# Schematic2.net
KiCad netlist of a schematic drawn in Altium Designer
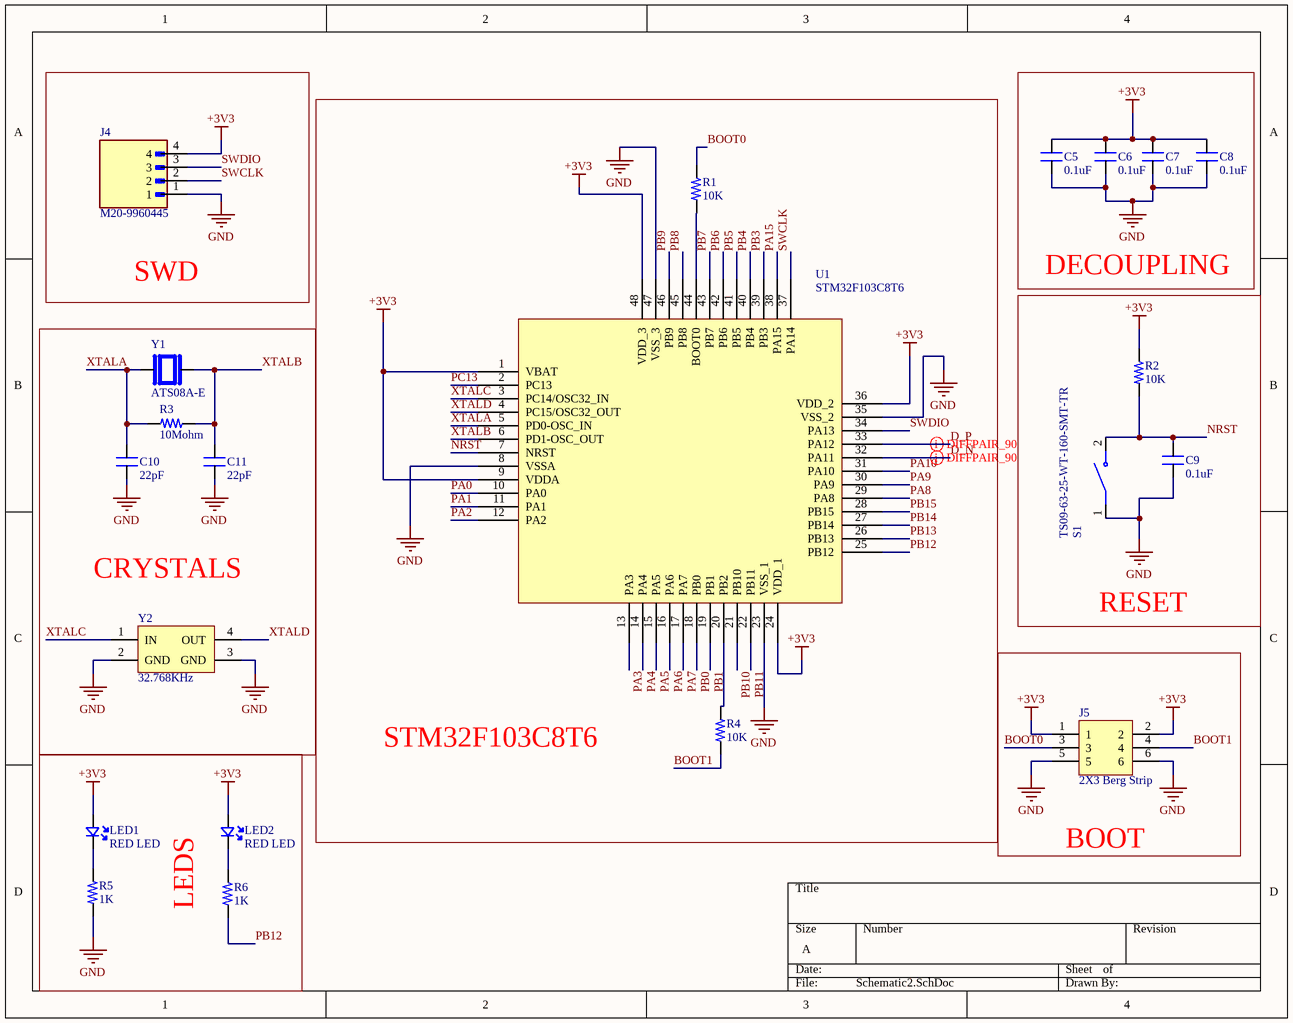
[diagram p0: Schematic2.SchDoc]

(export (version "E")
  (design (tool "Eeschema 10.0.6"))
  (components
    (comp (ref "C5")
      (value "0.1uF")
      (footprint "CAP_0805")
      (description "0.1µF ±5% 50V Ceramic Capacitor X7R 0805 (2012 Metric)")
      (fields
        (field (name "MANUFACTURER") "KEMET")
        (field (name "MANUFACTURING PART NUMBER") "C0805C104J5RACTU")
      )
      (libsource (lib "STM_INT_LIB") (part "CAP_0.1uF-50V-5%-0805"))
    )
    (comp (ref "C6")
      (value "0.1uF")
      (footprint "CAP_0805")
      (description "0.1µF ±5% 50V Ceramic Capacitor X7R 0805 (2012 Metric)")
      (fields
        (field (name "MANUFACTURER") "KEMET")
        (field (name "MANUFACTURING PART NUMBER") "C0805C104J5RACTU")
      )
      (libsource (lib "STM_INT_LIB") (part "CAP_0.1uF-50V-5%-0805"))
    )
    (comp (ref "C7")
      (value "0.1uF")
      (footprint "CAP_0805")
      (description "0.1µF ±5% 50V Ceramic Capacitor X7R 0805 (2012 Metric)")
      (fields
        (field (name "MANUFACTURER") "KEMET")
        (field (name "MANUFACTURING PART NUMBER") "C0805C104J5RACTU")
      )
      (libsource (lib "STM_INT_LIB") (part "CAP_0.1uF-50V-5%-0805"))
    )
    (comp (ref "C8")
      (value "0.1uF")
      (footprint "CAP_0805")
      (description "0.1µF ±5% 50V Ceramic Capacitor X7R 0805 (2012 Metric)")
      (fields
        (field (name "MANUFACTURER") "KEMET")
        (field (name "MANUFACTURING PART NUMBER") "C0805C104J5RACTU")
      )
      (libsource (lib "STM_INT_LIB") (part "CAP_0.1uF-50V-5%-0805"))
    )
    (comp (ref "C9")
      (value "0.1uF")
      (footprint "CAP_0805")
      (description "0.1µF ±5% 50V Ceramic Capacitor X7R 0805 (2012 Metric)")
      (fields
        (field (name "MANUFACTURER") "KEMET")
        (field (name "MANUFACTURING PART NUMBER") "C0805C104J5RACTU")
      )
      (libsource (lib "STM_INT_LIB") (part "CAP_0.1uF-50V-5%-0805"))
    )
    (comp (ref "C10")
      (value "22pF")
      (footprint "CAP_0805")
      (description "22pF ±5% 50V Ceramic Capacitor C0G, NP0 0805 (2012 Metric)")
      (fields
        (field (name "MANUFACTURER") "KEMET")
        (field (name "MANUFACTURER PART NUMBER") "C0805C220J5GACTU")
      )
      (libsource (lib "STM_INT_LIB") (part "CAP_22pF-50V-5%-0805"))
    )
    (comp (ref "C11")
      (value "22pF")
      (footprint "CAP_0805")
      (description "22pF ±5% 50V Ceramic Capacitor C0G, NP0 0805 (2012 Metric)")
      (fields
        (field (name "MANUFACTURER") "KEMET")
        (field (name "MANUFACTURER PART NUMBER") "C0805C220J5GACTU")
      )
      (libsource (lib "STM_INT_LIB") (part "CAP_22pF-50V-5%-0805"))
    )
    (comp (ref "J4")
      (value "M20-9960445")
      (footprint "HARWIN_M20-9960445")
      (fields (field (name "MF") "Harwin"))
      (libsource (lib "4 pin horizontal header") (part "M20-9960445"))
    )
    (comp (ref "J5")
      (value "2X3 Berg Strip")
      (footprint "CON6_100_59D78_TH_ST_Duplicate")
      (description "6 pin, 2 row, 2.54mm pitch bergstrip")
      (fields (field (name "MANUFACTURER") "NA"))
      (libsource (lib "STM_INT_LIB") (part "CON-BS-PLG_2X3-100-TH-ST"))
    )
    (comp (ref "LED1")
      (value "RED LED")
      (footprint "LED_0805")
      (description "Red 621nm LED Indication - Discrete 2V 0805 (2012 Metric)")
      (fields
        (field (name "MANUFACTURER") "Lite-On Inc.")
        (field (name "MANUFACTURER PART NUMBER") "LTST-C170EKT")
      )
      (libsource (lib "STM_INT_LIB") (part "LED-RED_10mA-0805"))
    )
    (comp (ref "LED2")
      (value "RED LED")
      (footprint "LED_0805")
      (description "Red 621nm LED Indication - Discrete 2V 0805 (2012 Metric)")
      (fields
        (field (name "MANUFACTURER") "Lite-On Inc.")
        (field (name "MANUFACTURER PART NUMBER") "LTST-C170EKT")
      )
      (libsource (lib "STM_INT_LIB") (part "LED-RED_10mA-0805"))
    )
    (comp (ref "R1")
      (value "10K")
      (footprint "RES_0805")
      (description "10 kOhms ±1% 0.125W, 1/8W Chip Resistor 0805 (2012 Metric) Moisture Resistant Thick Film")
      (fields
        (field (name "MANUFACTURER") "Yageo")
        (field (name "MANUFACTURING PART NUMBER") "RC0805FR-0710KL")
      )
      (libsource (lib "STM_INT_LIB") (part "RES_10K-0.125W-1%-0805"))
    )
    (comp (ref "R2")
      (value "10K")
      (footprint "RES_0805")
      (description "10 kOhms ±1% 0.125W, 1/8W Chip Resistor 0805 (2012 Metric) Moisture Resistant Thick Film")
      (fields
        (field (name "MANUFACTURER") "Yageo")
        (field (name "MANUFACTURING PART NUMBER") "RC0805FR-0710KL")
      )
      (libsource (lib "STM_INT_LIB") (part "RES_10K-0.125W-1%-0805"))
    )
    (comp (ref "R3")
      (value "10Mohm")
      (footprint "RES_0805")
      (fields
        (field (name "MANUFACTURER") "Rohm Semiconductor")
        (field (name "MANUFACTURING PART NUMBER") "KTR10EZPF1005")
      )
      (libsource (lib "STM_INT_LIB") (part "RES_10MOHM-0.125W-1%-0805"))
    )
    (comp (ref "R4")
      (value "10K")
      (footprint "RES_0805")
      (description "10 kOhms ±1% 0.125W, 1/8W Chip Resistor 0805 (2012 Metric) Moisture Resistant Thick Film")
      (fields
        (field (name "MANUFACTURER") "Yageo")
        (field (name "MANUFACTURING PART NUMBER") "RC0805FR-0710KL")
      )
      (libsource (lib "STM_INT_LIB") (part "RES_10K-0.125W-1%-0805"))
    )
    (comp (ref "R5")
      (value "1K")
      (footprint "RES_0805")
      (description "1 kOhms ±1% 0.125W, 1/8W Chip Resistor 0805 (2012 Metric) Moisture Resistant Thick Film")
      (fields (field (name "MANUFACTURER") "垈㎵á") (field (name "MANUFACTURER PART NUMBER") "RC0805FR-071KL"))
      (libsource (lib "STM_INT_LIB") (part "RES_1K-0.125W-1%-0805"))
    )
    (comp (ref "R6")
      (value "1K")
      (footprint "RES_0805")
      (description "1 kOhms ±1% 0.125W, 1/8W Chip Resistor 0805 (2012 Metric) Moisture Resistant Thick Film")
      (fields (field (name "MANUFACTURER") "垈㎵á") (field (name "MANUFACTURER PART NUMBER") "RC0805FR-071KL"))
      (libsource (lib "STM_INT_LIB") (part "RES_1K-0.125W-1%-0805"))
    )
    (comp (ref "S1")
      (value "TS09-63-25-WT-160-SMT-TR")
      (footprint "SW_TS09-63-25-WT-160-SMT-TR")
      (description "6.1 x 3.7 mm, 2.5 mm Actuator Height, 160 gf, White, Surface Mount, SPST, Tactile Switch")
      (fields (field (name "MF") "Same Sky"))
      (libsource (lib "TS09-63-25-WT-160-SMT-TR") (part "TS09-63-25-WT-160-SMT-TR"))
    )
    (comp (ref "U1")
      (value "STM32F103C8T6")
      (footprint "LQFP-48_19.6_393_58X11_SMD")
      (description "ARM® Cortex®-M3 STM32F1 Microcontroller IC 32-Bit 72MHz 64KB (64K x 8) FLASH")
      (fields (field (name "MANUFACTURER") "STMicroelectronics"))
      (libsource (lib "STM_INT_LIB") (part "IC-STM32F103C8T6 _1"))
    )
    (comp (ref "Y1")
      (value "ATS08A-E")
      (footprint "XTAL_HC49P488W43L1085T450H368")
      (description "8 MHz Â±30ppm Crystal 20pF 60 Ohms HC-49/US")
      (fields (field (name "MF") "CTS"))
      (libsource (lib "ATS08A-E") (part "ATS08A-E"))
    )
    (comp (ref "Y2")
      (value "32.768KHz")
      (footprint "XTAL_MC-405 32.7680K-G3")
      (description "Crystals SMD AT XTL MHZ +/-50PPM 12.5 PF 250 T/R")
      (fields
        (field (name "MANUFACTURER") "Epson")
        (field (name "MANUFACTURING PART NUMBER") "MC-405 32.7680K-G3: ROHS")
      )
      (libsource (lib "STM_INT_LIB") (part "XTAL_32.768KHz-MC-405 32.7680K-G3"))
    )
  )
  (nets
    (net (code "1") (name "+3V3") (class "Default")
      (node (ref "C5") (pin "2") (pinfunction "2_2") (pintype "passive"))
      (node (ref "C6") (pin "2") (pinfunction "2_2") (pintype "passive"))
      (node (ref "C7") (pin "2") (pinfunction "2_2") (pintype "passive"))
      (node (ref "C8") (pin "2") (pinfunction "2_2") (pintype "passive"))
      (node (ref "J4") (pin "4") (pinfunction "4_4") (pintype "passive"))
      (node (ref "J5") (pin "1") (pinfunction "1_1") (pintype "passive"))
      (node (ref "J5") (pin "2") (pinfunction "2_2") (pintype "passive"))
      (node (ref "LED1") (pin "A") (pinfunction "A_A") (pintype "passive"))
      (node (ref "LED2") (pin "A") (pinfunction "A_A") (pintype "passive"))
      (node (ref "R2") (pin "2") (pinfunction "2_2") (pintype "passive"))
      (node (ref "U1") (pin "1") (pinfunction "VBAT_1") (pintype "passive"))
      (node (ref "U1") (pin "24") (pinfunction "VDD_1_24") (pintype "passive"))
      (node (ref "U1") (pin "36") (pinfunction "VDD_2_36") (pintype "passive"))
      (node (ref "U1") (pin "48") (pinfunction "VDD_3_48") (pintype "passive"))
      (node (ref "U1") (pin "9") (pinfunction "VDDA_9") (pintype "passive"))
    )
    (net (code "2") (name "/BOOT0") (class "Default")
      (node (ref "J5") (pin "3") (pinfunction "3_3") (pintype "passive"))
      (node (ref "R1") (pin "2") (pinfunction "2_2") (pintype "passive"))
    )
    (net (code "3") (name "/BOOT1") (class "Default")
      (node (ref "J5") (pin "4") (pinfunction "4_4") (pintype "passive"))
      (node (ref "R4") (pin "1") (pinfunction "1_1") (pintype "passive"))
    )
    (net (code "4") (name "/D_N") (class "Default")
      (node (ref "U1") (pin "32") (pinfunction "PA11_32") (pintype "passive"))
    )
    (net (code "5") (name "/D_P") (class "Default")
      (node (ref "U1") (pin "33") (pinfunction "PA12_33") (pintype "passive"))
    )
    (net (code "6") (name "/NRST") (class "Default")
      (node (ref "C9") (pin "2") (pinfunction "2_2") (pintype "passive"))
      (node (ref "R2") (pin "1") (pinfunction "1_1") (pintype "passive"))
      (node (ref "S1") (pin "2") (pinfunction "2_2") (pintype "passive"))
      (node (ref "U1") (pin "7") (pinfunction "NRST_7") (pintype "passive"))
    )
    (net (code "7") (name "/PA0") (class "Default")
      (node (ref "U1") (pin "10") (pinfunction "PA0_10") (pintype "passive"))
    )
    (net (code "8") (name "/PA1") (class "Default")
      (node (ref "U1") (pin "11") (pinfunction "PA1_11") (pintype "passive"))
    )
    (net (code "9") (name "/PA2") (class "Default")
      (node (ref "U1") (pin "12") (pinfunction "PA2_12") (pintype "passive"))
    )
    (net (code "10") (name "/PA3") (class "Default")
      (node (ref "U1") (pin "13") (pinfunction "PA3_13") (pintype "passive"))
    )
    (net (code "11") (name "/PA4") (class "Default")
      (node (ref "U1") (pin "14") (pinfunction "PA4_14") (pintype "passive"))
    )
    (net (code "12") (name "/PA5") (class "Default")
      (node (ref "U1") (pin "15") (pinfunction "PA5_15") (pintype "passive"))
    )
    (net (code "13") (name "/PA6") (class "Default")
      (node (ref "U1") (pin "16") (pinfunction "PA6_16") (pintype "passive"))
    )
    (net (code "14") (name "/PA7") (class "Default")
      (node (ref "U1") (pin "17") (pinfunction "PA7_17") (pintype "passive"))
    )
    (net (code "15") (name "/PA8") (class "Default")
      (node (ref "U1") (pin "29") (pinfunction "PA8_29") (pintype "passive"))
    )
    (net (code "16") (name "/PA9") (class "Default")
      (node (ref "U1") (pin "30") (pinfunction "PA9_30") (pintype "passive"))
    )
    (net (code "17") (name "/PA10") (class "Default")
      (node (ref "U1") (pin "31") (pinfunction "PA10_31") (pintype "passive"))
    )
    (net (code "18") (name "/PA15") (class "Default")
      (node (ref "U1") (pin "38") (pinfunction "PA15_38") (pintype "passive"))
    )
    (net (code "19") (name "/PB0") (class "Default")
      (node (ref "U1") (pin "18") (pinfunction "PB0_18") (pintype "passive"))
    )
    (net (code "20") (name "/PB1") (class "Default")
      (node (ref "U1") (pin "19") (pinfunction "PB1_19") (pintype "passive"))
    )
    (net (code "21") (name "/PB3") (class "Default")
      (node (ref "U1") (pin "39") (pinfunction "PB3_39") (pintype "passive"))
    )
    (net (code "22") (name "/PB4") (class "Default")
      (node (ref "U1") (pin "40") (pinfunction "PB4_40") (pintype "passive"))
    )
    (net (code "23") (name "/PB5") (class "Default")
      (node (ref "U1") (pin "41") (pinfunction "PB5_41") (pintype "passive"))
    )
    (net (code "24") (name "/PB6") (class "Default")
      (node (ref "U1") (pin "42") (pinfunction "PB6_42") (pintype "passive"))
    )
    (net (code "25") (name "/PB7") (class "Default")
      (node (ref "U1") (pin "43") (pinfunction "PB7_43") (pintype "passive"))
    )
    (net (code "26") (name "/PB8") (class "Default")
      (node (ref "U1") (pin "45") (pinfunction "PB8_45") (pintype "passive"))
    )
    (net (code "27") (name "/PB9") (class "Default")
      (node (ref "U1") (pin "46") (pinfunction "PB9_46") (pintype "passive"))
    )
    (net (code "28") (name "/PB10") (class "Default")
      (node (ref "U1") (pin "21") (pinfunction "PB10_21") (pintype "passive"))
    )
    (net (code "29") (name "/PB11") (class "Default")
      (node (ref "U1") (pin "22") (pinfunction "PB11_22") (pintype "passive"))
    )
    (net (code "30") (name "/PB12") (class "Default")
      (node (ref "R6") (pin "1") (pinfunction "1_1") (pintype "passive"))
      (node (ref "U1") (pin "25") (pinfunction "PB12_25") (pintype "passive"))
    )
    (net (code "31") (name "/PB13") (class "Default")
      (node (ref "U1") (pin "26") (pinfunction "PB13_26") (pintype "passive"))
    )
    (net (code "32") (name "/PB14") (class "Default")
      (node (ref "U1") (pin "27") (pinfunction "PB14_27") (pintype "passive"))
    )
    (net (code "33") (name "/PB15") (class "Default")
      (node (ref "U1") (pin "28") (pinfunction "PB15_28") (pintype "passive"))
    )
    (net (code "34") (name "/PC13") (class "Default")
      (node (ref "U1") (pin "2") (pinfunction "PC13_2") (pintype "passive"))
    )
    (net (code "35") (name "/SWCLK") (class "Default")
      (node (ref "J4") (pin "2") (pinfunction "2_2") (pintype "passive"))
      (node (ref "U1") (pin "37") (pinfunction "PA14_37") (pintype "passive"))
    )
    (net (code "36") (name "/SWDIO") (class "Default")
      (node (ref "J4") (pin "3") (pinfunction "3_3") (pintype "passive"))
      (node (ref "U1") (pin "34") (pinfunction "PA13_34") (pintype "passive"))
    )
    (net (code "37") (name "/XTALA") (class "Default")
      (node (ref "C10") (pin "2") (pinfunction "2_2") (pintype "passive"))
      (node (ref "R3") (pin "1") (pinfunction "1_1") (pintype "passive"))
      (node (ref "U1") (pin "5") (pinfunction "PD0-OSC_IN_5") (pintype "passive"))
      (node (ref "Y1") (pin "1") (pinfunction "1_1") (pintype "passive"))
    )
    (net (code "38") (name "/XTALB") (class "Default")
      (node (ref "C11") (pin "2") (pinfunction "2_2") (pintype "passive"))
      (node (ref "R3") (pin "2") (pinfunction "2_2") (pintype "passive"))
      (node (ref "U1") (pin "6") (pinfunction "PD1-OSC_OUT_6") (pintype "passive"))
      (node (ref "Y1") (pin "2") (pinfunction "2_2") (pintype "passive"))
    )
    (net (code "39") (name "/XTALC") (class "Default")
      (node (ref "U1") (pin "3") (pinfunction "PC14/OSC32_IN_3") (pintype "passive"))
      (node (ref "Y2") (pin "1") (pinfunction "IN_1") (pintype "passive"))
    )
    (net (code "40") (name "/XTALD") (class "Default")
      (node (ref "U1") (pin "4") (pinfunction "PC15/OSC32_OUT_4") (pintype "passive"))
      (node (ref "Y2") (pin "4") (pinfunction "OUT_4") (pintype "passive"))
    )
    (net (code "41") (name "GND") (class "Default")
      (node (ref "C10") (pin "1") (pinfunction "1_1") (pintype "passive"))
      (node (ref "C11") (pin "1") (pinfunction "1_1") (pintype "passive"))
      (node (ref "C5") (pin "1") (pinfunction "1_1") (pintype "passive"))
      (node (ref "C6") (pin "1") (pinfunction "1_1") (pintype "passive"))
      (node (ref "C7") (pin "1") (pinfunction "1_1") (pintype "passive"))
      (node (ref "C8") (pin "1") (pinfunction "1_1") (pintype "passive"))
      (node (ref "C9") (pin "1") (pinfunction "1_1") (pintype "passive"))
      (node (ref "J4") (pin "1") (pinfunction "1_1") (pintype "passive"))
      (node (ref "J5") (pin "5") (pinfunction "5_5") (pintype "passive"))
      (node (ref "J5") (pin "6") (pinfunction "6_6") (pintype "passive"))
      (node (ref "R5") (pin "1") (pinfunction "1_1") (pintype "passive"))
      (node (ref "S1") (pin "1") (pinfunction "1_1") (pintype "passive"))
      (node (ref "U1") (pin "23") (pinfunction "VSS_1_23") (pintype "passive"))
      (node (ref "U1") (pin "35") (pinfunction "VSS_2_35") (pintype "passive"))
      (node (ref "U1") (pin "47") (pinfunction "VSS_3_47") (pintype "passive"))
      (node (ref "U1") (pin "8") (pinfunction "VSSA_8") (pintype "passive"))
      (node (ref "Y2") (pin "2") (pinfunction "GND_2") (pintype "passive"))
      (node (ref "Y2") (pin "3") (pinfunction "GND_3") (pintype "passive"))
    )
    (net (code "42") (name "Net-(LED1-PadK)") (class "Default")
      (node (ref "LED1") (pin "K") (pinfunction "K_K") (pintype "passive"))
      (node (ref "R5") (pin "2") (pinfunction "2_2") (pintype "passive"))
    )
    (net (code "43") (name "Net-(LED2-PadK)") (class "Default")
      (node (ref "LED2") (pin "K") (pinfunction "K_K") (pintype "passive"))
      (node (ref "R6") (pin "2") (pinfunction "2_2") (pintype "passive"))
    )
    (net (code "44") (name "Net-(U1-BOOT0)") (class "Default")
      (node (ref "R1") (pin "1") (pinfunction "1_1") (pintype "passive"))
      (node (ref "U1") (pin "44") (pinfunction "BOOT0_44") (pintype "passive"))
    )
    (net (code "45") (name "Net-(U1-PB2)") (class "Default")
      (node (ref "R4") (pin "2") (pinfunction "2_2") (pintype "passive"))
      (node (ref "U1") (pin "20") (pinfunction "PB2_20") (pintype "passive"))
    )
  )
)
